# Buffer_EXC.net
KiCad netlist of a schematic drawn in Altium Designer
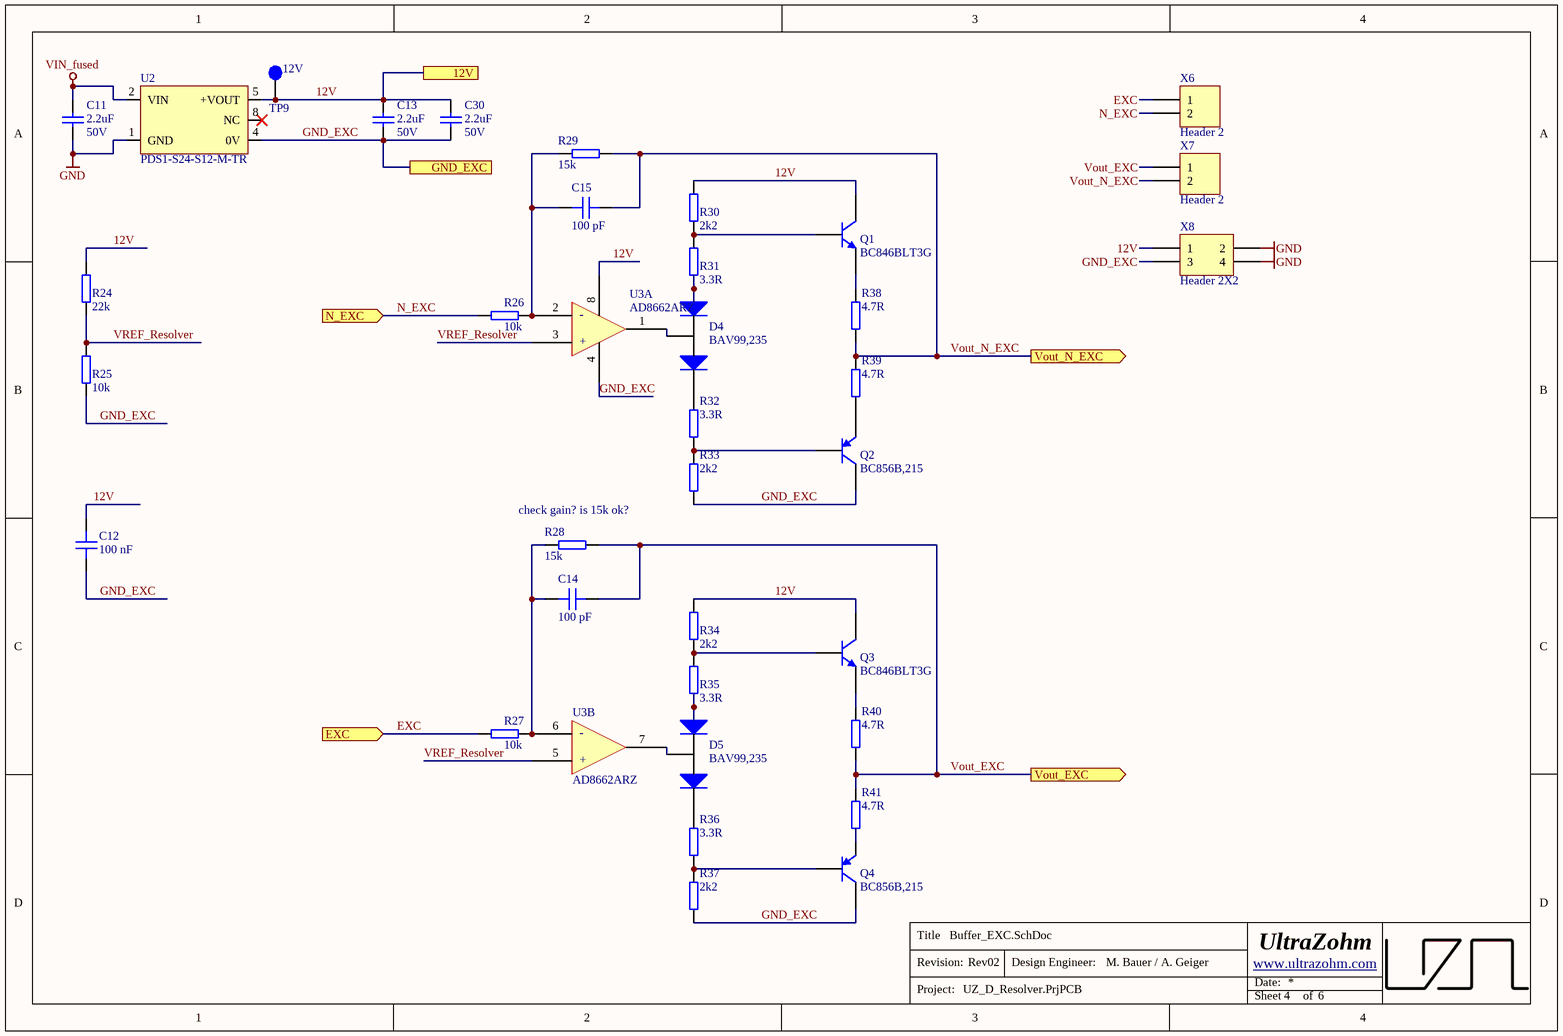
[diagram p0: Buffer_EXC.SchDoc]

(export (version "E")
  (design (tool "Eeschema 10.0.6"))
  (components
    (comp (ref "C11")
      (value "2.2uF")
      (footprint "RES_1206")
      (description "Capacitor")
      (fields (field (name "VOLTAGE") "50V") (field (name "LCSC PART NUMBER") "C50254"))
      (libsource (lib "Componentes_SOC") (part "Cap_1206"))
    )
    (comp (ref "C12")
      (value "100 nF")
      (footprint "C_0603")
      (description "Capacitor 0603, 50 VDC, 100 nF, X7R")
      (fields
        (field (name "MANUFACTURER PART NUMBER") "CC0603KRX7R9BB104")
        (field (name "MANUFACTURER") "YAGEO")
        (field (name "CREATED FROM") "AGeiger")
      )
      (libsource (lib "user") (part "Capacitor"))
    )
    (comp (ref "C13")
      (value "2.2uF")
      (footprint "RES_1206")
      (description "Capacitor")
      (fields (field (name "VOLTAGE") "50V") (field (name "LCSC PART NUMBER") "C50254"))
      (libsource (lib "Componentes_SOC") (part "Cap_1206"))
    )
    (comp (ref "C14")
      (value "100 pF")
      (footprint "C_0603")
      (description "50V 100pF C0G ±5% 0603 Multilayer Ceramic Capacitors MLCC - SMD/SMT ROHS")
      (fields
        (field (name "MANUFACTURER PART NUMBER") "CL10C101JB8NNNC")
        (field (name "MANUFACTURER") "Samsung Electro-Mechanics")
        (field (name "CREATED FROM") "AGeiger")
      )
      (libsource (lib "user") (part "Capacitor"))
    )
    (comp (ref "C15")
      (value "100 pF")
      (footprint "C_0603")
      (description "50V 100pF C0G ±5% 0603 Multilayer Ceramic Capacitors MLCC - SMD/SMT ROHS")
      (fields
        (field (name "MANUFACTURER PART NUMBER") "CL10C101JB8NNNC")
        (field (name "MANUFACTURER") "Samsung Electro-Mechanics")
        (field (name "CREATED FROM") "AGeiger")
      )
      (libsource (lib "user") (part "Capacitor"))
    )
    (comp (ref "C30")
      (value "2.2uF")
      (footprint "RES_1206")
      (description "Capacitor")
      (fields (field (name "VOLTAGE") "50V") (field (name "LCSC PART NUMBER") "C50254"))
      (libsource (lib "Componentes_SOC") (part "Cap_1206"))
    )
    (comp (ref "D4")
      (value "BAV99,235")
      (footprint "SOT-23")
      (description "DIODE ARRAY GP 100V 215MA SOT23")
      (fields (field (name "MF") "Nexperia") (field (name "LCSC PART NUMBER") "C2500"))
      (libsource (lib "Componentes_SOC") (part "Diode Array"))
    )
    (comp (ref "D5")
      (value "BAV99,235")
      (footprint "SOT-23")
      (description "DIODE ARRAY GP 100V 215MA SOT23")
      (fields (field (name "MF") "Nexperia") (field (name "LCSC PART NUMBER") "C2500"))
      (libsource (lib "Componentes_SOC") (part "Diode Array"))
    )
    (comp (ref "Q1")
      (value "BC846BLT3G")
      (footprint "SOT-23")
      (description "NPN Bipolar Transistor")
      (fields (field (name "MF") "ON Semiconductor") (field (name "LCSC PART NUMBER") "C513271"))
      (libsource (lib "Componentes_SOC") (part "NPN Transistor BC846"))
    )
    (comp (ref "Q2")
      (value "BC856B,215")
      (footprint "SOT-23")
      (description "PNP Bipolar Transistor")
      (fields (field (name "MF") "Nexperia") (field (name "LCSC PART NUMBER") "C109310"))
      (libsource (lib "Componentes_SOC") (part "PNP Transistor BC846"))
    )
    (comp (ref "Q3")
      (value "BC846BLT3G")
      (footprint "SOT-23")
      (description "NPN Bipolar Transistor")
      (fields (field (name "MF") "ON Semiconductor") (field (name "LCSC PART NUMBER") "C513271"))
      (libsource (lib "Componentes_SOC") (part "NPN Transistor BC846"))
    )
    (comp (ref "Q4")
      (value "BC856B,215")
      (footprint "SOT-23")
      (description "PNP Bipolar Transistor")
      (fields (field (name "MF") "Nexperia") (field (name "LCSC PART NUMBER") "C109310"))
      (libsource (lib "Componentes_SOC") (part "PNP Transistor BC846"))
    )
    (comp (ref "R24")
      (value "22k")
      (footprint "RES 0603_1608")
      (description "SMD resistor E24 series")
      (fields
        (field (name "MANUFACTURER PART NUMBER") "RK73B1JTTD223J")
        (field (name "MANUFACTURER") "KOA Speer")
        (field (name "CREATED FROM") "MGremer")
      )
      (libsource (lib "user") (part "Resistor"))
    )
    (comp (ref "R25")
      (value "10k")
      (footprint "RES 0603_1608")
      (description "SMD resistor E24 series")
      (fields
        (field (name "MANUFACTURER PART NUMBER") "RK73B1JTTD103J")
        (field (name "MANUFACTURER") "KOA Speer")
        (field (name "CREATED FROM") "MGremer")
      )
      (libsource (lib "user") (part "Resistor"))
    )
    (comp (ref "R26")
      (value "10k")
      (footprint "RES 0603_1608")
      (description "SMD resistor E24 series")
      (fields
        (field (name "MANUFACTURER PART NUMBER") "RK73B1JTTD103J")
        (field (name "MANUFACTURER") "KOA Speer")
        (field (name "CREATED FROM") "MGremer")
      )
      (libsource (lib "user") (part "Resistor"))
    )
    (comp (ref "R27")
      (value "10k")
      (footprint "RES 0603_1608")
      (description "SMD resistor E24 series")
      (fields
        (field (name "MANUFACTURER PART NUMBER") "RK73B1JTTD103J")
        (field (name "MANUFACTURER") "KOA Speer")
        (field (name "CREATED FROM") "MGremer")
      )
      (libsource (lib "user") (part "Resistor"))
    )
    (comp (ref "R28")
      (value "15k")
      (footprint "RES 0603_1608")
      (description "SMD resistor E24 series")
      (fields
        (field (name "MANUFACTURER PART NUMBER") "RK73B1JTTD153J")
        (field (name "MANUFACTURER") "KOA Speer")
        (field (name "CREATED FROM") "MGremer")
      )
      (libsource (lib "user") (part "Resistor"))
    )
    (comp (ref "R29")
      (value "15k")
      (footprint "RES 0603_1608")
      (description "SMD resistor E24 series")
      (fields
        (field (name "MANUFACTURER PART NUMBER") "RK73B1JTTD153J")
        (field (name "MANUFACTURER") "KOA Speer")
        (field (name "CREATED FROM") "MGremer")
      )
      (libsource (lib "user") (part "Resistor"))
    )
    (comp (ref "R30")
      (value "2k2")
      (footprint "RES 0603_1608")
      (description "SMD resistor E24 series")
      (fields
        (field (name "MANUFACTURER PART NUMBER") "RK73B1JTTD222J")
        (field (name "MANUFACTURER") "KOA Speer")
        (field (name "CREATED FROM") "MGremer")
      )
      (libsource (lib "user") (part "Resistor"))
    )
    (comp (ref "R31")
      (value "3.3R")
      (footprint "RES 0603_1608")
      (description "SMD resistor E24 series")
      (fields
        (field (name "MANUFACTURER PART NUMBER") "RK73B1JTTDD3R3J")
        (field (name "MANUFACTURER") "KOA Speer")
        (field (name "CREATED FROM") "MGremer")
      )
      (libsource (lib "user") (part "Resistor"))
    )
    (comp (ref "R32")
      (value "3.3R")
      (footprint "RES 0603_1608")
      (description "SMD resistor E24 series")
      (fields
        (field (name "MANUFACTURER PART NUMBER") "RK73B1JTTDD3R3J")
        (field (name "MANUFACTURER") "KOA Speer")
        (field (name "CREATED FROM") "MGremer")
      )
      (libsource (lib "user") (part "Resistor"))
    )
    (comp (ref "R33")
      (value "2k2")
      (footprint "RES 0603_1608")
      (description "SMD resistor E24 series")
      (fields
        (field (name "MANUFACTURER PART NUMBER") "RK73B1JTTD222J")
        (field (name "MANUFACTURER") "KOA Speer")
        (field (name "CREATED FROM") "MGremer")
      )
      (libsource (lib "user") (part "Resistor"))
    )
    (comp (ref "R34")
      (value "2k2")
      (footprint "RES 0603_1608")
      (description "SMD resistor E24 series")
      (fields
        (field (name "MANUFACTURER PART NUMBER") "RK73B1JTTD222J")
        (field (name "MANUFACTURER") "KOA Speer")
        (field (name "CREATED FROM") "MGremer")
      )
      (libsource (lib "user") (part "Resistor"))
    )
    (comp (ref "R35")
      (value "3.3R")
      (footprint "RES 0603_1608")
      (description "SMD resistor E24 series")
      (fields
        (field (name "MANUFACTURER PART NUMBER") "RK73B1JTTDD3R3J")
        (field (name "MANUFACTURER") "KOA Speer")
        (field (name "CREATED FROM") "MGremer")
      )
      (libsource (lib "user") (part "Resistor"))
    )
    (comp (ref "R36")
      (value "3.3R")
      (footprint "RES 0603_1608")
      (description "SMD resistor E24 series")
      (fields
        (field (name "MANUFACTURER PART NUMBER") "RK73B1JTTDD3R3J")
        (field (name "MANUFACTURER") "KOA Speer")
        (field (name "CREATED FROM") "MGremer")
      )
      (libsource (lib "user") (part "Resistor"))
    )
    (comp (ref "R37")
      (value "2k2")
      (footprint "RES 0603_1608")
      (description "SMD resistor E24 series")
      (fields
        (field (name "MANUFACTURER PART NUMBER") "RK73B1JTTD222J")
        (field (name "MANUFACTURER") "KOA Speer")
        (field (name "CREATED FROM") "MGremer")
      )
      (libsource (lib "user") (part "Resistor"))
    )
    (comp (ref "R38")
      (value "4.7R")
      (footprint "RES 0603_1608")
      (description "SMD resistor E24 series")
      (fields
        (field (name "MANUFACTURER PART NUMBER") "RK73B1JTTDD4R7J")
        (field (name "MANUFACTURER") "KOA Speer")
        (field (name "CREATED FROM") "MGremer")
      )
      (libsource (lib "user") (part "Resistor"))
    )
    (comp (ref "R39")
      (value "4.7R")
      (footprint "RES 0603_1608")
      (description "SMD resistor E24 series")
      (fields
        (field (name "MANUFACTURER PART NUMBER") "RK73B1JTTDD4R7J")
        (field (name "MANUFACTURER") "KOA Speer")
        (field (name "CREATED FROM") "MGremer")
      )
      (libsource (lib "user") (part "Resistor"))
    )
    (comp (ref "R40")
      (value "4.7R")
      (footprint "RES 0603_1608")
      (description "SMD resistor E24 series")
      (fields
        (field (name "MANUFACTURER PART NUMBER") "RK73B1JTTDD4R7J")
        (field (name "MANUFACTURER") "KOA Speer")
        (field (name "CREATED FROM") "MGremer")
      )
      (libsource (lib "user") (part "Resistor"))
    )
    (comp (ref "R41")
      (value "4.7R")
      (footprint "RES 0603_1608")
      (description "SMD resistor E24 series")
      (fields
        (field (name "MANUFACTURER PART NUMBER") "RK73B1JTTDD4R7J")
        (field (name "MANUFACTURER") "KOA Speer")
        (field (name "CREATED FROM") "MGremer")
      )
      (libsource (lib "user") (part "Resistor"))
    )
    (comp (ref "TP9")
      (value "12V")
      (footprint "TP_1mm")
      (description "Testpoint 1mm")
      (fields (field (name "CREATED") "2018_06_25_AGeiger"))
      (libsource (lib "UltraZOhm_CarrierBoard") (part "TP_1mm"))
    )
    (comp (ref "U2")
      (value "PDS1-S24-S12-M-TR")
      (footprint "DC/DC 24V-->12V 1W Aislado")
      (description "DC DC CONVERTER 12V 1W")
      (fields (field (name "MF") "CUI") (field (name "LCSC PART NUMBER") "C5707797"))
      (libsource (lib "Componentes_SOC") (part "DC/DC +12V 1W"))
    )
    (comp (ref "U3")
      (value "AD8662ARZ")
      (footprint "SOIC8_N")
      (description "IC OPAMP GP 2 CIRCUIT 14SOIC")
      (fields (field (name "MF") "Analog Devices") (field (name "LCSC PART NUMBER") "C28133"))
      (libsource (lib "Componentes_SOC") (part "AD8662"))
    )
    (comp (ref "X6")
      (value "Header 2")
      (footprint "HDR1X2")
      (description "Header, 2-Pin")
      (fields (field (name "PUBLISHER") "Altium Limited"))
      (libsource (lib "Miscellaneous Connectors") (part "Header 2"))
    )
    (comp (ref "X7")
      (value "Header 2")
      (footprint "HDR1X2")
      (description "Header, 2-Pin")
      (fields (field (name "PUBLISHER") "Altium Limited"))
      (libsource (lib "Miscellaneous Connectors") (part "Header 2"))
    )
    (comp (ref "X8")
      (value "Header 2X2")
      (footprint "HDR2X2")
      (description "Header, 2-Pin, Dual row")
      (fields (field (name "PUBLISHER") "Altium Limited"))
      (libsource (lib "Miscellaneous Connectors") (part "Header 2X2"))
    )
  )
  (nets
    (net (code "1") (name "/12V") (class "Default")
      (node (ref "C12") (pin "1") (pinfunction "1_1") (pintype "passive"))
      (node (ref "C13") (pin "1") (pinfunction "1_1") (pintype "passive"))
      (node (ref "C30") (pin "1") (pinfunction "1_1") (pintype "passive"))
      (node (ref "Q1") (pin "3") (pinfunction "C_3") (pintype "passive"))
      (node (ref "Q3") (pin "3") (pinfunction "C_3") (pintype "passive"))
      (node (ref "R24") (pin "2") (pinfunction "2_2") (pintype "passive"))
      (node (ref "R30") (pin "2") (pinfunction "2_2") (pintype "passive"))
      (node (ref "R34") (pin "2") (pinfunction "2_2") (pintype "passive"))
      (node (ref "TP9") (pin "1") (pintype "passive"))
      (node (ref "U2") (pin "5") (pinfunction "+VOUT_5") (pintype "passive"))
      (node (ref "U3") (pin "8") (pinfunction "v-_8") (pintype "passive"))
      (node (ref "X8") (pin "1") (pinfunction "1_1") (pintype "passive"))
    )
    (net (code "2") (name "/EXC") (class "Default")
      (node (ref "R27") (pin "2") (pinfunction "2_2") (pintype "passive"))
      (node (ref "X6") (pin "1") (pinfunction "1_1") (pintype "passive"))
    )
    (net (code "3") (name "/GND_EXC") (class "Default")
      (node (ref "C12") (pin "2") (pinfunction "2_2") (pintype "passive"))
      (node (ref "C13") (pin "2") (pinfunction "2_2") (pintype "passive"))
      (node (ref "C30") (pin "2") (pinfunction "2_2") (pintype "passive"))
      (node (ref "Q2") (pin "3") (pinfunction "C_3") (pintype "passive"))
      (node (ref "Q4") (pin "3") (pinfunction "C_3") (pintype "passive"))
      (node (ref "R25") (pin "1") (pinfunction "1_1") (pintype "passive"))
      (node (ref "R33") (pin "2") (pinfunction "2_2") (pintype "passive"))
      (node (ref "R37") (pin "2") (pinfunction "2_2") (pintype "passive"))
      (node (ref "U2") (pin "4") (pinfunction "0V_4") (pintype "passive"))
      (node (ref "U3") (pin "4") (pinfunction "v+_4") (pintype "passive"))
      (node (ref "X8") (pin "3") (pinfunction "3_3") (pintype "passive"))
    )
    (net (code "4") (name "/N_EXC") (class "Default")
      (node (ref "R26") (pin "2") (pinfunction "2_2") (pintype "passive"))
      (node (ref "X6") (pin "2") (pinfunction "2_2") (pintype "passive"))
    )
    (net (code "5") (name "/VREF_Resolver") (class "Default")
      (node (ref "R24") (pin "1") (pinfunction "1_1") (pintype "passive"))
      (node (ref "R25") (pin "2") (pinfunction "2_2") (pintype "passive"))
      (node (ref "U3") (pin "3") (pinfunction "+in_a_3") (pintype "passive"))
      (node (ref "U3") (pin "5") (pinfunction "+in_b_5") (pintype "passive"))
    )
    (net (code "6") (name "/Vout_EXC") (class "Default")
      (node (ref "C14") (pin "2") (pinfunction "2_2") (pintype "passive"))
      (node (ref "R28") (pin "2") (pinfunction "2_2") (pintype "passive"))
      (node (ref "R40") (pin "2") (pinfunction "2_2") (pintype "passive"))
      (node (ref "R41") (pin "1") (pinfunction "1_1") (pintype "passive"))
      (node (ref "X7") (pin "1") (pinfunction "1_1") (pintype "passive"))
    )
    (net (code "7") (name "/Vout_N_EXC") (class "Default")
      (node (ref "C15") (pin "2") (pinfunction "2_2") (pintype "passive"))
      (node (ref "R29") (pin "2") (pinfunction "2_2") (pintype "passive"))
      (node (ref "R38") (pin "2") (pinfunction "2_2") (pintype "passive"))
      (node (ref "R39") (pin "1") (pinfunction "1_1") (pintype "passive"))
      (node (ref "X7") (pin "2") (pinfunction "2_2") (pintype "passive"))
    )
    (net (code "8") (name "GND") (class "Default")
      (node (ref "C11") (pin "2") (pinfunction "2_2") (pintype "passive"))
      (node (ref "U2") (pin "1") (pinfunction "GND_1") (pintype "passive"))
      (node (ref "X8") (pin "2") (pinfunction "2_2") (pintype "passive"))
      (node (ref "X8") (pin "4") (pinfunction "4_4") (pintype "passive"))
    )
    (net (code "9") (name "Net-(D4-Pad1)") (class "Default")
      (node (ref "D4") (pin "1") (pintype "passive"))
      (node (ref "R31") (pin "1") (pinfunction "1_1") (pintype "passive"))
    )
    (net (code "10") (name "Net-(D4-Pad2)") (class "Default")
      (node (ref "D4") (pin "2") (pintype "passive"))
      (node (ref "R32") (pin "1") (pinfunction "1_1") (pintype "passive"))
    )
    (net (code "11") (name "Net-(D5-Pad1)") (class "Default")
      (node (ref "D5") (pin "1") (pintype "passive"))
      (node (ref "R35") (pin "1") (pinfunction "1_1") (pintype "passive"))
    )
    (net (code "12") (name "Net-(D5-Pad2)") (class "Default")
      (node (ref "D5") (pin "2") (pintype "passive"))
      (node (ref "R36") (pin "1") (pinfunction "1_1") (pintype "passive"))
    )
    (net (code "13") (name "Net-(Q1-B)") (class "Default")
      (node (ref "Q1") (pin "1") (pinfunction "B_1") (pintype "passive"))
      (node (ref "R30") (pin "1") (pinfunction "1_1") (pintype "passive"))
      (node (ref "R31") (pin "2") (pinfunction "2_2") (pintype "passive"))
    )
    (net (code "14") (name "Net-(Q1-E)") (class "Default")
      (node (ref "Q1") (pin "2") (pinfunction "E_2") (pintype "passive"))
      (node (ref "R38") (pin "1") (pinfunction "1_1") (pintype "passive"))
    )
    (net (code "15") (name "Net-(Q2-B)") (class "Default")
      (node (ref "Q2") (pin "1") (pinfunction "B_1") (pintype "passive"))
      (node (ref "R32") (pin "2") (pinfunction "2_2") (pintype "passive"))
      (node (ref "R33") (pin "1") (pinfunction "1_1") (pintype "passive"))
    )
    (net (code "16") (name "Net-(Q2-E)") (class "Default")
      (node (ref "Q2") (pin "2") (pinfunction "E_2") (pintype "passive"))
      (node (ref "R39") (pin "2") (pinfunction "2_2") (pintype "passive"))
    )
    (net (code "17") (name "Net-(Q3-B)") (class "Default")
      (node (ref "Q3") (pin "1") (pinfunction "B_1") (pintype "passive"))
      (node (ref "R34") (pin "1") (pinfunction "1_1") (pintype "passive"))
      (node (ref "R35") (pin "2") (pinfunction "2_2") (pintype "passive"))
    )
    (net (code "18") (name "Net-(Q3-E)") (class "Default")
      (node (ref "Q3") (pin "2") (pinfunction "E_2") (pintype "passive"))
      (node (ref "R40") (pin "1") (pinfunction "1_1") (pintype "passive"))
    )
    (net (code "19") (name "Net-(Q4-B)") (class "Default")
      (node (ref "Q4") (pin "1") (pinfunction "B_1") (pintype "passive"))
      (node (ref "R36") (pin "2") (pinfunction "2_2") (pintype "passive"))
      (node (ref "R37") (pin "1") (pinfunction "1_1") (pintype "passive"))
    )
    (net (code "20") (name "Net-(Q4-E)") (class "Default")
      (node (ref "Q4") (pin "2") (pinfunction "E_2") (pintype "passive"))
      (node (ref "R41") (pin "2") (pinfunction "2_2") (pintype "passive"))
    )
    (net (code "21") (name "Net-(U3A--in_a)") (class "Default")
      (node (ref "C15") (pin "1") (pinfunction "1_1") (pintype "passive"))
      (node (ref "R26") (pin "1") (pinfunction "1_1") (pintype "passive"))
      (node (ref "R29") (pin "1") (pinfunction "1_1") (pintype "passive"))
      (node (ref "U3") (pin "2") (pinfunction "-in_a_2") (pintype "passive"))
    )
    (net (code "22") (name "Net-(U3A-out_a)") (class "Default")
      (node (ref "D4") (pin "3") (pintype "passive"))
      (node (ref "U3") (pin "1") (pinfunction "out_a_1") (pintype "passive"))
    )
    (net (code "23") (name "Net-(U3B--in_b)") (class "Default")
      (node (ref "C14") (pin "1") (pinfunction "1_1") (pintype "passive"))
      (node (ref "R27") (pin "1") (pinfunction "1_1") (pintype "passive"))
      (node (ref "R28") (pin "1") (pinfunction "1_1") (pintype "passive"))
      (node (ref "U3") (pin "6") (pinfunction "-in_b_6") (pintype "passive"))
    )
    (net (code "24") (name "Net-(U3B-out_b)") (class "Default")
      (node (ref "D5") (pin "3") (pintype "passive"))
      (node (ref "U3") (pin "7") (pinfunction "out_b_7") (pintype "passive"))
    )
    (net (code "25") (name "VIN_fused") (class "Default")
      (node (ref "C11") (pin "1") (pinfunction "1_1") (pintype "passive"))
      (node (ref "U2") (pin "2") (pinfunction "VIN_2") (pintype "passive"))
    )
    (net (code "26") (name "unconnected-(U2-NC-Pad8)") (class "Default")
      (node (ref "U2") (pin "8") (pinfunction "NC_8") (pintype "passive+no_connect"))
    )
    (net (code "27") (name "unconnected-(U2-NC-Pad15)") (class "Default")
      (node (ref "U2") (pin "15") (pinfunction "NC_15") (pintype "passive"))
    )
    (net (code "28") (name "unconnected-(U2-NC-Pad16)") (class "Default")
      (node (ref "U2") (pin "16") (pinfunction "NC_16") (pintype "passive"))
    )
    (net (code "29") (name "unconnected-(U2-NC-Pad17)") (class "Default")
      (node (ref "U2") (pin "17") (pinfunction "NC_17") (pintype "passive"))
    )
    (net (code "30") (name "unconnected-(U2-NC-Pad26)") (class "Default")
      (node (ref "U2") (pin "26") (pinfunction "NC_26") (pintype "passive"))
    )
    (net (code "31") (name "unconnected-(U2-NC-Pad27)") (class "Default")
      (node (ref "U2") (pin "27") (pinfunction "NC_27") (pintype "passive"))
    )
  )
)
